# Vibration.net
KiCad netlist of a schematic drawn in EAGLE
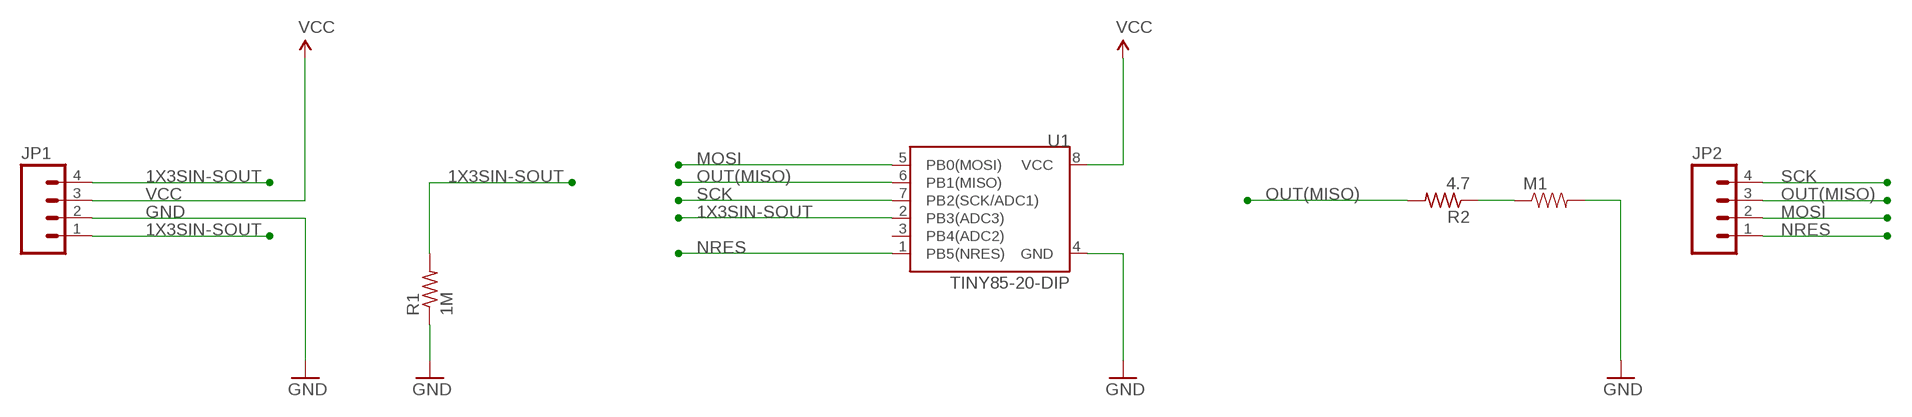
[diagram p0: schematic, sheet 1]

(export (version "E")
  (design (tool "Eeschema 10.0.6"))
  (components
    (comp (ref "JP1")
      (value "M04PTH")
      (footprint "eagle-import:1X04")
      (libsource (lib "eagle-import") (part "M04PTH"))
    )
    (comp (ref "JP2")
      (value "M04PTH")
      (footprint "eagle-import:1X04")
      (libsource (lib "eagle-import") (part "M04PTH"))
    )
    (comp (ref "M1")
      (value "10OHM-1/4W-5%(PTH)VERT-KIT")
      (footprint "eagle-import:AXIAL-0.1EZ")
      (libsource (lib "eagle-import") (part "10OHM-1/4W-5%(PTH)VERT-KIT"))
    )
    (comp (ref "R1")
      (value "1M")
      (footprint "eagle-import:R0603")
      (libsource (lib "eagle-import") (part "R-US_R0603"))
    )
    (comp (ref "R2")
      (value "4.7")
      (footprint "eagle-import:R0603")
      (libsource (lib "eagle-import") (part "R-US_R0603"))
    )
    (comp (ref "U1")
      (value "TINY85-20-DIP")
      (footprint "eagle-import:DIP08")
      (libsource (lib "eagle-import") (part "ATTINY45TINY85-20-DIP"))
    )
  )
  (nets
    (net (code "1") (name "/1X3SIN-SOUT") (class "Default")
      (node (ref "JP1") (pin "1") (pinfunction "1_1") (pintype "passive"))
      (node (ref "JP1") (pin "4") (pinfunction "4_4") (pintype "passive"))
      (node (ref "R1") (pin "2") (pinfunction "2_2") (pintype "passive"))
      (node (ref "U1") (pin "2") (pinfunction "PB3(ADC3)_2") (pintype "bidirectional"))
    )
    (net (code "2") (name "/MOSI") (class "Default")
      (node (ref "JP2") (pin "2") (pinfunction "2_2") (pintype "passive"))
      (node (ref "U1") (pin "5") (pinfunction "PB0(MOSI)_5") (pintype "bidirectional"))
    )
    (net (code "3") (name "/NRES") (class "Default")
      (node (ref "JP2") (pin "1") (pinfunction "1_1") (pintype "passive"))
      (node (ref "U1") (pin "1") (pinfunction "PB5(NRES)_1") (pintype "bidirectional"))
    )
    (net (code "4") (name "/OUT(MISO)") (class "Default")
      (node (ref "JP2") (pin "3") (pinfunction "3_3") (pintype "passive"))
      (node (ref "R2") (pin "2") (pinfunction "2_2") (pintype "passive"))
      (node (ref "U1") (pin "6") (pinfunction "PB1(MISO)_6") (pintype "bidirectional"))
    )
    (net (code "5") (name "/SCK") (class "Default")
      (node (ref "JP2") (pin "4") (pinfunction "4_4") (pintype "passive"))
      (node (ref "U1") (pin "7") (pinfunction "PB2(SCK/ADC1)_7") (pintype "bidirectional"))
    )
    (net (code "6") (name "GND") (class "Default")
      (node (ref "JP1") (pin "2") (pinfunction "2_2") (pintype "passive"))
      (node (ref "M1") (pin "P$2") (pinfunction "2_P$2") (pintype "passive"))
      (node (ref "R1") (pin "1") (pinfunction "1_1") (pintype "passive"))
      (node (ref "U1") (pin "4") (pinfunction "GND_4") (pintype "bidirectional"))
    )
    (net (code "7") (name "Net-(M1-1)") (class "Default")
      (node (ref "M1") (pin "P$1") (pinfunction "1_P$1") (pintype "passive"))
      (node (ref "R2") (pin "1") (pinfunction "1_1") (pintype "passive"))
    )
    (net (code "8") (name "VCC") (class "Default")
      (node (ref "JP1") (pin "3") (pinfunction "3_3") (pintype "passive"))
      (node (ref "U1") (pin "8") (pinfunction "VCC_8") (pintype "bidirectional"))
    )
    (net (code "9") (name "unconnected-(U1-PB4(ADC2)-Pad3)") (class "Default")
      (node (ref "U1") (pin "3") (pinfunction "PB4(ADC2)_3") (pintype "bidirectional"))
    )
  )
)
